# board_RGB.net
KiCad netlist of a schematic drawn in EAGLE
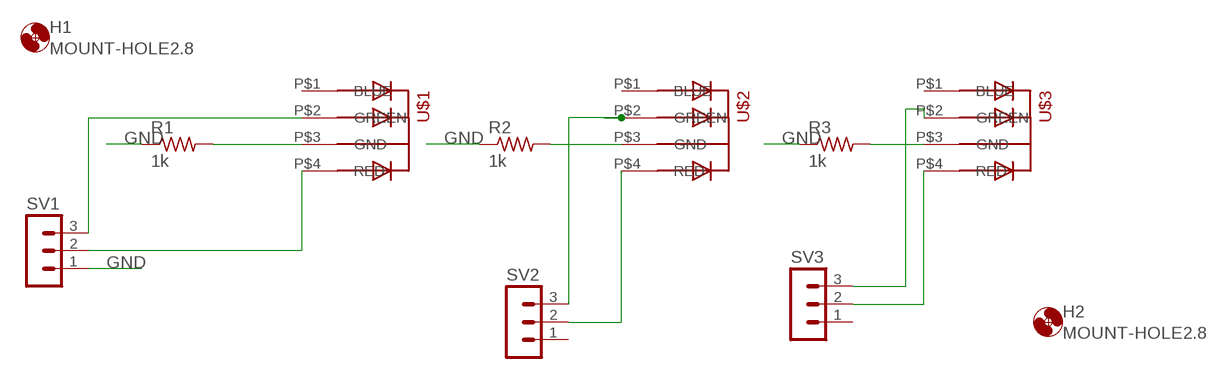
[diagram p0: schematic, sheet 1]

(export (version "E")
  (design (tool "Eeschema 10.0.6"))
  (components
    (comp (ref "H1")
      (value "MOUNT-HOLE2.8")
      (footprint "eagle-import:2,8")
      (libsource (lib "eagle-import") (part "MOUNT-HOLE2.8"))
    )
    (comp (ref "H2")
      (value "MOUNT-HOLE2.8")
      (footprint "eagle-import:2,8")
      (libsource (lib "eagle-import") (part "MOUNT-HOLE2.8"))
    )
    (comp (ref "R1")
      (value "1k")
      (footprint "eagle-import:0207_10")
      (libsource (lib "eagle-import") (part "R-US_0207/10"))
    )
    (comp (ref "R2")
      (value "1k")
      (footprint "eagle-import:0207_10")
      (libsource (lib "eagle-import") (part "R-US_0207/10"))
    )
    (comp (ref "R3")
      (value "1k")
      (footprint "eagle-import:0207_10")
      (libsource (lib "eagle-import") (part "R-US_0207/10"))
    )
    (comp (ref "SV1")
      (value "MA03-1")
      (footprint "eagle-import:MA03-1")
      (libsource (lib "eagle-import") (part "MA03-1"))
    )
    (comp (ref "SV2")
      (value "MA03-1")
      (footprint "eagle-import:MA03-1")
      (libsource (lib "eagle-import") (part "MA03-1"))
    )
    (comp (ref "SV3")
      (value "MA03-1")
      (footprint "eagle-import:MA03-1")
      (libsource (lib "eagle-import") (part "MA03-1"))
    )
    (comp (ref "U$1")
      (value "5MMRGBLED")
      (footprint "eagle-import:LED5MMRGB")
      (libsource (lib "eagle-import") (part "5MMRGBLED"))
    )
    (comp (ref "U$2")
      (value "5MMRGBLED")
      (footprint "eagle-import:LED5MMRGB")
      (libsource (lib "eagle-import") (part "5MMRGBLED"))
    )
    (comp (ref "U$3")
      (value "5MMRGBLED")
      (footprint "eagle-import:LED5MMRGB")
      (libsource (lib "eagle-import") (part "5MMRGBLED"))
    )
  )
  (nets
    (net (code "1") (name "/GND") (class "Default")
      (node (ref "R1") (pin "1") (pinfunction "1_1") (pintype "passive"))
      (node (ref "R2") (pin "1") (pinfunction "1_1") (pintype "passive"))
      (node (ref "R3") (pin "1") (pinfunction "1_1") (pintype "passive"))
      (node (ref "SV1") (pin "1") (pinfunction "1_1") (pintype "passive"))
    )
    (net (code "2") (name "Net-(U$1-GND)") (class "Default")
      (node (ref "R1") (pin "2") (pinfunction "2_2") (pintype "passive"))
      (node (ref "U$1") (pin "P$3") (pinfunction "GND_P$3") (pintype "bidirectional"))
    )
    (net (code "3") (name "Net-(U$1-GREEN)") (class "Default")
      (node (ref "SV1") (pin "3") (pinfunction "3_3") (pintype "passive"))
      (node (ref "U$1") (pin "P$2") (pinfunction "GREEN_P$2") (pintype "bidirectional"))
    )
    (net (code "4") (name "Net-(U$1-RED)") (class "Default")
      (node (ref "SV1") (pin "2") (pinfunction "2_2") (pintype "passive"))
      (node (ref "U$1") (pin "P$4") (pinfunction "RED_P$4") (pintype "bidirectional"))
    )
    (net (code "5") (name "Net-(U$2-GND)") (class "Default")
      (node (ref "R2") (pin "2") (pinfunction "2_2") (pintype "passive"))
      (node (ref "U$2") (pin "P$3") (pinfunction "GND_P$3") (pintype "bidirectional"))
    )
    (net (code "6") (name "Net-(U$2-GREEN)") (class "Default")
      (node (ref "SV2") (pin "3") (pinfunction "3_3") (pintype "passive"))
      (node (ref "U$2") (pin "P$2") (pinfunction "GREEN_P$2") (pintype "bidirectional"))
    )
    (net (code "7") (name "Net-(U$2-RED)") (class "Default")
      (node (ref "SV2") (pin "2") (pinfunction "2_2") (pintype "passive"))
      (node (ref "U$2") (pin "P$4") (pinfunction "RED_P$4") (pintype "bidirectional"))
    )
    (net (code "8") (name "Net-(U$3-GND)") (class "Default")
      (node (ref "R3") (pin "2") (pinfunction "2_2") (pintype "passive"))
      (node (ref "U$3") (pin "P$3") (pinfunction "GND_P$3") (pintype "bidirectional"))
    )
    (net (code "9") (name "Net-(U$3-GREEN)") (class "Default")
      (node (ref "SV3") (pin "3") (pinfunction "3_3") (pintype "passive"))
      (node (ref "U$3") (pin "P$2") (pinfunction "GREEN_P$2") (pintype "bidirectional"))
    )
    (net (code "10") (name "Net-(U$3-RED)") (class "Default")
      (node (ref "SV3") (pin "2") (pinfunction "2_2") (pintype "passive"))
      (node (ref "U$3") (pin "P$4") (pinfunction "RED_P$4") (pintype "bidirectional"))
    )
    (net (code "11") (name "unconnected-(SV2-Pad1)") (class "Default")
      (node (ref "SV2") (pin "1") (pinfunction "1_1") (pintype "passive"))
    )
    (net (code "12") (name "unconnected-(SV3-Pad1)") (class "Default")
      (node (ref "SV3") (pin "1") (pinfunction "1_1") (pintype "passive"))
    )
    (net (code "13") (name "unconnected-(U$1-BLUE-PadP$1)") (class "Default")
      (node (ref "U$1") (pin "P$1") (pinfunction "BLUE_P$1") (pintype "bidirectional"))
    )
    (net (code "14") (name "unconnected-(U$2-BLUE-PadP$1)") (class "Default")
      (node (ref "U$2") (pin "P$1") (pinfunction "BLUE_P$1") (pintype "bidirectional"))
    )
    (net (code "15") (name "unconnected-(U$3-BLUE-PadP$1)") (class "Default")
      (node (ref "U$3") (pin "P$1") (pinfunction "BLUE_P$1") (pintype "bidirectional"))
    )
  )
)
